# old_line_kick.net
KiCad netlist of a schematic drawn in EAGLE
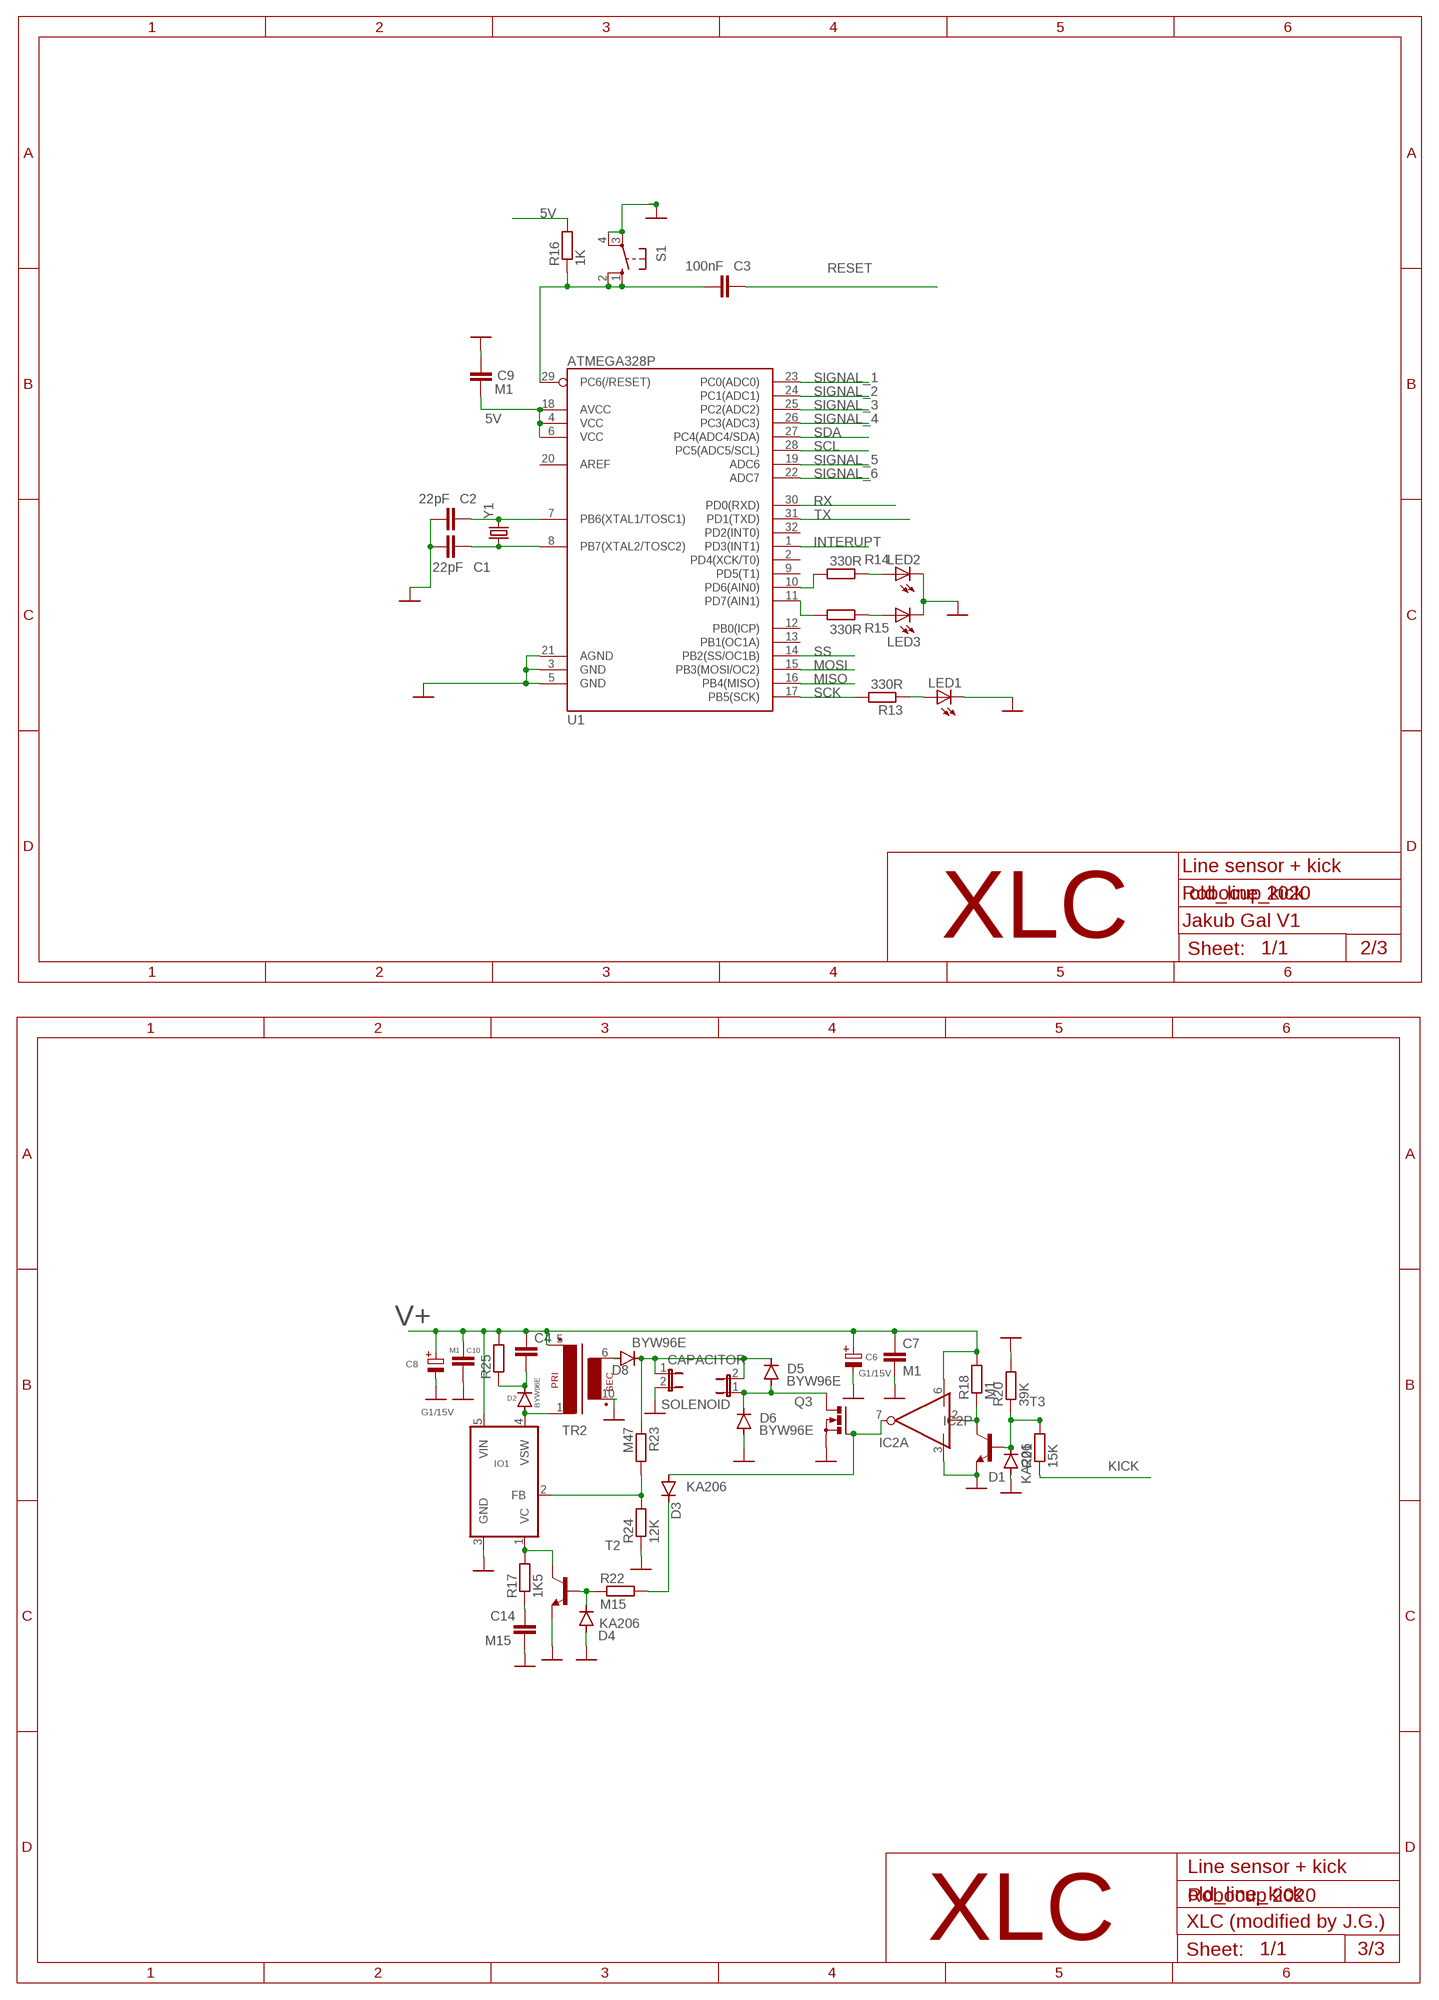
[diagram p0: schematic, sheet 1, part 1 of 2]
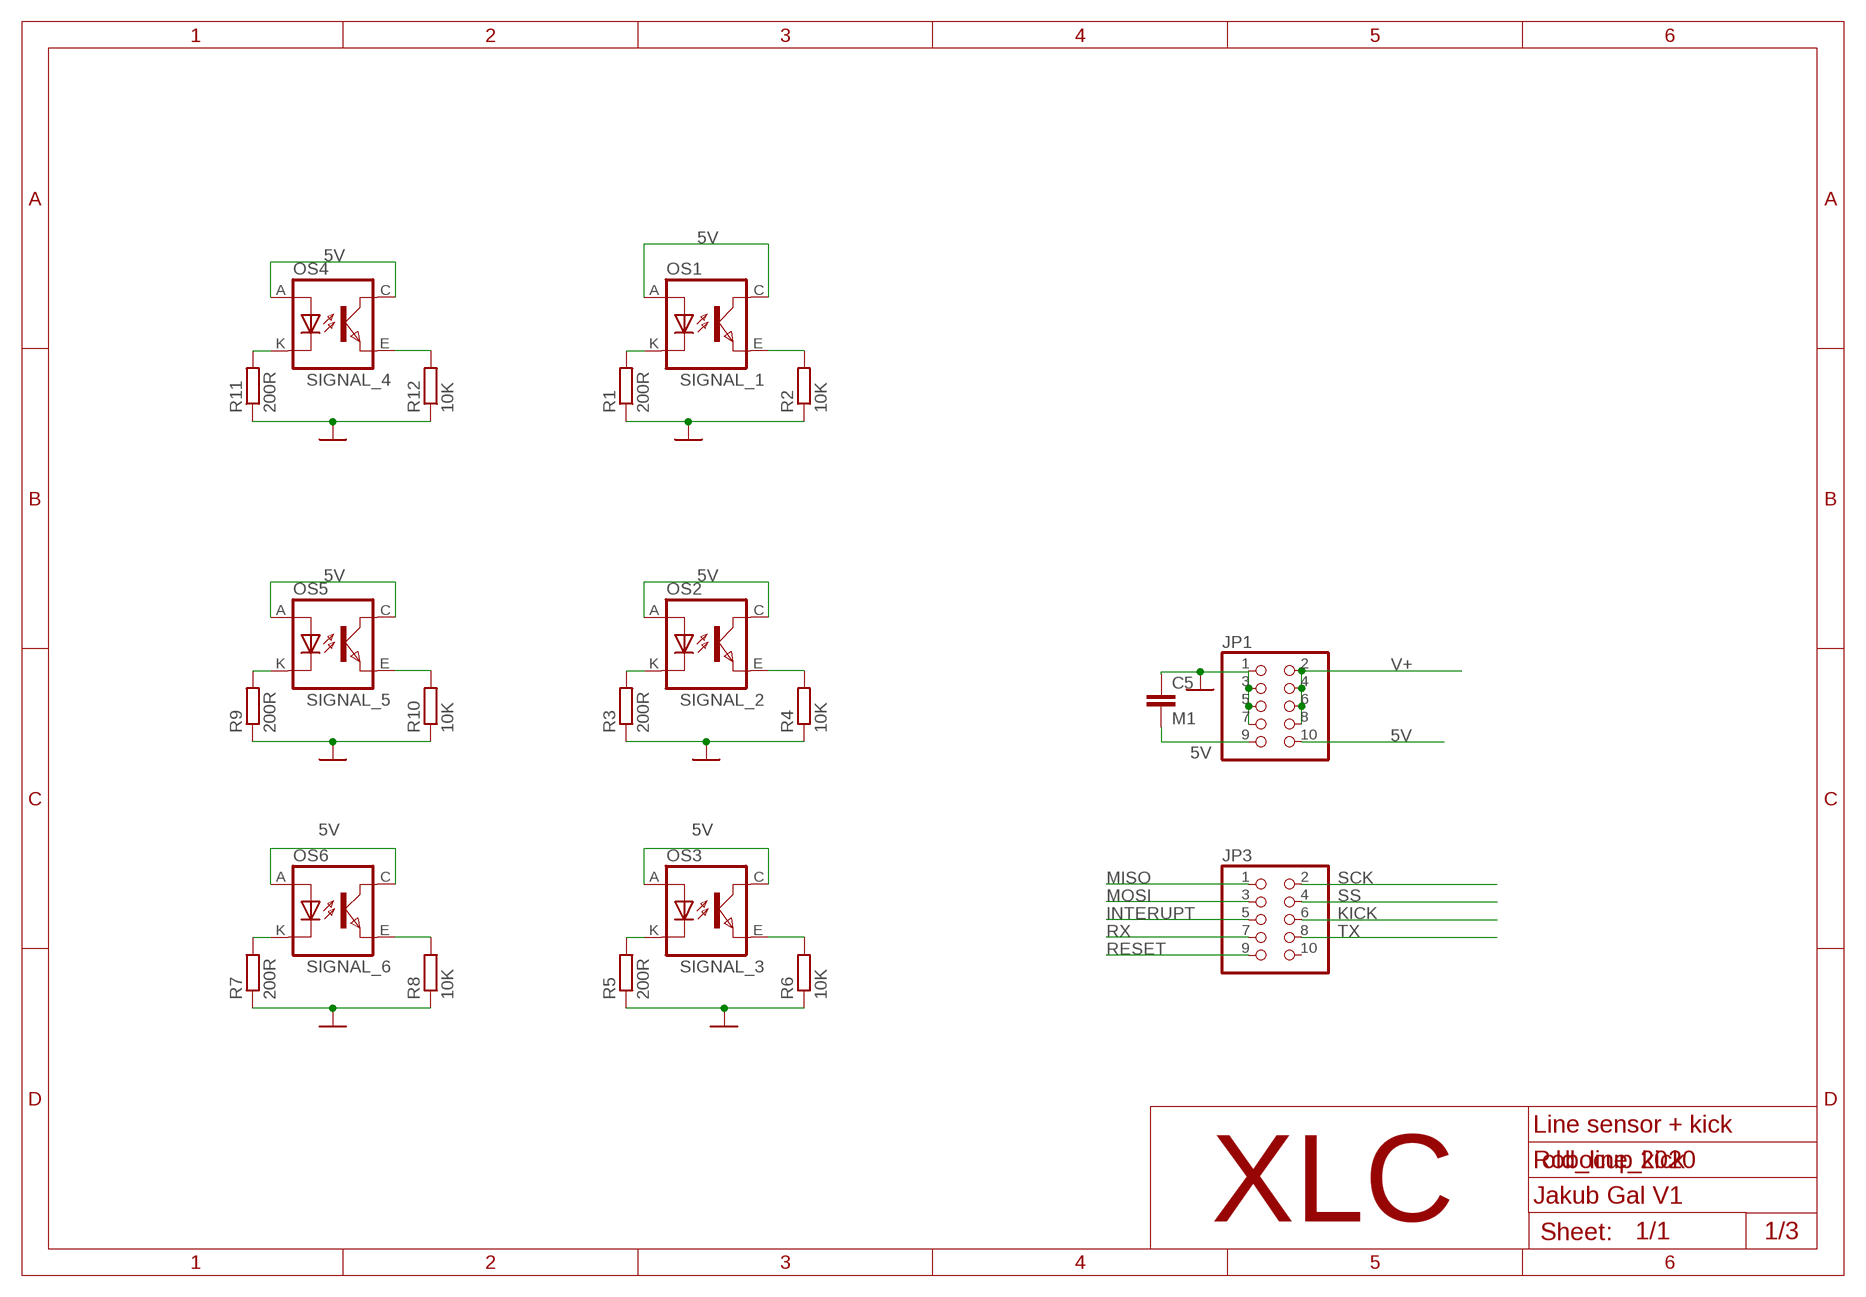
[diagram p1: schematic, sheet 1, part 2 of 2]

(export (version "E")
  (design (tool "Eeschema 10.0.6"))
  (components
    (comp (ref "C1")
      (value "22pF")
      (footprint "eagle-import:C0603")
      (libsource (lib "eagle-import") (part "rcl@1_C-EUC0603"))
    )
    (comp (ref "C2")
      (value "22pF")
      (footprint "eagle-import:C0603")
      (libsource (lib "eagle-import") (part "rcl@1_C-EUC0603"))
    )
    (comp (ref "C3")
      (value "100nF")
      (footprint "eagle-import:C0603")
      (libsource (lib "eagle-import") (part "rcl@1_C-EUC0603"))
    )
    (comp (ref "C4")
      (value "C-EU075-052X106")
      (footprint "eagle-import:C075-052X106")
      (libsource (lib "eagle-import") (part "C-EU075-052X106"))
    )
    (comp (ref "C5")
      (value "M1")
      (footprint "eagle-import:C0603")
      (libsource (lib "eagle-import") (part "C-EUC0603"))
    )
    (comp (ref "C6")
      (value "G1/15V")
      (footprint "eagle-import:E-2,5_7-RAD")
      (libsource (lib "eagle-import") (part "KOND-ELEKT-2,5/7"))
    )
    (comp (ref "C7")
      (value "M1")
      (footprint "eagle-import:C0805K")
      (libsource (lib "eagle-import") (part "resistor_C-EUC0805K"))
    )
    (comp (ref "C8")
      (value "G1/15V")
      (footprint "eagle-import:E-2,5_7-RAD")
      (libsource (lib "eagle-import") (part "KOND-ELEKT-2,5/7"))
    )
    (comp (ref "C9")
      (value "M1")
      (footprint "eagle-import:C0603")
      (libsource (lib "eagle-import") (part "rcl@1_C-EUC0603"))
    )
    (comp (ref "C10")
      (value "M1")
      (footprint "eagle-import:C0805K")
      (libsource (lib "eagle-import") (part "resistor_C-EUC0805K"))
    )
    (comp (ref "C14")
      (value "M15")
      (footprint "eagle-import:C1206")
      (libsource (lib "eagle-import") (part "resistor_C-EUC1206"))
    )
    (comp (ref "CAPACITOR")
      (value "JP1E")
      (footprint "eagle-import:JP1")
      (libsource (lib "eagle-import") (part "JP1E"))
    )
    (comp (ref "D1")
      (value "KA206")
      (footprint "eagle-import:D-7.5")
      (libsource (lib "eagle-import") (part "DIODE-D-7.5"))
    )
    (comp (ref "D2")
      (value "BYW96E")
      (footprint "eagle-import:SOD64-10")
      (libsource (lib "eagle-import") (part "BYW96"))
    )
    (comp (ref "D3")
      (value "KA206")
      (footprint "eagle-import:D-7.5")
      (libsource (lib "eagle-import") (part "DIODE-D-7.5"))
    )
    (comp (ref "D4")
      (value "KA206")
      (footprint "eagle-import:D-7.5")
      (libsource (lib "eagle-import") (part "DIODE-D-7.5"))
    )
    (comp (ref "D5")
      (value "BYW96E")
      (footprint "eagle-import:SOD64-10")
      (libsource (lib "eagle-import") (part "BYW96"))
    )
    (comp (ref "D6")
      (value "BYW96E")
      (footprint "eagle-import:SOD64-10")
      (libsource (lib "eagle-import") (part "BYW96"))
    )
    (comp (ref "D8")
      (value "BYW96E")
      (footprint "eagle-import:SOD64-10")
      (libsource (lib "eagle-import") (part "BYW96"))
    )
    (comp (ref "IC2")
      (value "MIC4423BM")
      (footprint "eagle-import:SO08")
      (libsource (lib "eagle-import") (part "MIC4423BM"))
    )
    (comp (ref "IO1")
      (value "LT1071V")
      (footprint "eagle-import:TO220-5P")
      (libsource (lib "eagle-import") (part "LT1071V"))
    )
    (comp (ref "JP1")
      (value "PINHD-2X5IDC")
      (footprint "eagle-import:2X05_IDC")
      (libsource (lib "eagle-import") (part "PINHD-2X5IDC"))
    )
    (comp (ref "JP3")
      (value "PINHD-2X5IDC")
      (footprint "eagle-import:2X05_IDC")
      (libsource (lib "eagle-import") (part "PINHD-2X5IDC"))
    )
    (comp (ref "LED1")
      (value "LEDCHIPLED_0603")
      (footprint "eagle-import:CHIPLED_0603")
      (libsource (lib "eagle-import") (part "LEDCHIPLED_0603"))
    )
    (comp (ref "LED2")
      (value "LEDCHIPLED_0603")
      (footprint "eagle-import:CHIPLED_0603")
      (libsource (lib "eagle-import") (part "LEDCHIPLED_0603"))
    )
    (comp (ref "LED3")
      (value "LEDCHIPLED_0603")
      (footprint "eagle-import:CHIPLED_0603")
      (libsource (lib "eagle-import") (part "LEDCHIPLED_0603"))
    )
    (comp (ref "OS1")
      (value "TCRT5000")
      (footprint "eagle-import:TCRT5000")
      (libsource (lib "eagle-import") (part "TCRT5000"))
    )
    (comp (ref "OS2")
      (value "TCRT5000")
      (footprint "eagle-import:TCRT5000")
      (libsource (lib "eagle-import") (part "TCRT5000"))
    )
    (comp (ref "OS3")
      (value "TCRT5000")
      (footprint "eagle-import:TCRT5000")
      (libsource (lib "eagle-import") (part "TCRT5000"))
    )
    (comp (ref "OS4")
      (value "TCRT5000")
      (footprint "eagle-import:TCRT5000")
      (fields (field (name "SPICEPREFIX") "O"))
      (libsource (lib "eagle-import") (part "TCRT5000"))
    )
    (comp (ref "OS5")
      (value "TCRT5000")
      (footprint "eagle-import:TCRT5000")
      (libsource (lib "eagle-import") (part "TCRT5000"))
    )
    (comp (ref "OS6")
      (value "TCRT5000")
      (footprint "eagle-import:TCRT5000")
      (fields (field (name "SPICEPREFIX") "O"))
      (libsource (lib "eagle-import") (part "TCRT5000"))
    )
    (comp (ref "Q3")
      (value "PMOSFET_NTO220BV")
      (footprint "eagle-import:TO220BV")
      (libsource (lib "eagle-import") (part "PMOSFET_NTO220BV"))
    )
    (comp (ref "R1")
      (value "200R")
      (footprint "eagle-import:R0603")
      (libsource (lib "eagle-import") (part "R-EU_R0603"))
    )
    (comp (ref "R2")
      (value "10K")
      (footprint "eagle-import:R0603")
      (libsource (lib "eagle-import") (part "R-EU_R0603"))
    )
    (comp (ref "R3")
      (value "200R")
      (footprint "eagle-import:R0603")
      (libsource (lib "eagle-import") (part "R-EU_R0603"))
    )
    (comp (ref "R4")
      (value "10K")
      (footprint "eagle-import:R0603")
      (libsource (lib "eagle-import") (part "R-EU_R0603"))
    )
    (comp (ref "R5")
      (value "200R")
      (footprint "eagle-import:R0603")
      (libsource (lib "eagle-import") (part "R-EU_R0603"))
    )
    (comp (ref "R6")
      (value "10K")
      (footprint "eagle-import:R0603")
      (libsource (lib "eagle-import") (part "R-EU_R0603"))
    )
    (comp (ref "R7")
      (value "200R")
      (footprint "eagle-import:R0603")
      (libsource (lib "eagle-import") (part "R-EU_R0603"))
    )
    (comp (ref "R8")
      (value "10K")
      (footprint "eagle-import:R0603")
      (libsource (lib "eagle-import") (part "R-EU_R0603"))
    )
    (comp (ref "R9")
      (value "200R")
      (footprint "eagle-import:R0603")
      (libsource (lib "eagle-import") (part "R-EU_R0603"))
    )
    (comp (ref "R10")
      (value "10K")
      (footprint "eagle-import:R0603")
      (libsource (lib "eagle-import") (part "R-EU_R0603"))
    )
    (comp (ref "R11")
      (value "200R")
      (footprint "eagle-import:R0603")
      (libsource (lib "eagle-import") (part "R-EU_R0603"))
    )
    (comp (ref "R12")
      (value "10K")
      (footprint "eagle-import:R0603")
      (libsource (lib "eagle-import") (part "R-EU_R0603"))
    )
    (comp (ref "R13")
      (value "330R")
      (footprint "eagle-import:R0603")
      (libsource (lib "eagle-import") (part "R-EU_R0603"))
    )
    (comp (ref "R14")
      (value "330R")
      (footprint "eagle-import:R0603")
      (libsource (lib "eagle-import") (part "R-EU_R0603"))
    )
    (comp (ref "R15")
      (value "330R")
      (footprint "eagle-import:R0603")
      (libsource (lib "eagle-import") (part "R-EU_R0603"))
    )
    (comp (ref "R16")
      (value "1K")
      (footprint "eagle-import:R0603")
      (libsource (lib "eagle-import") (part "R-EU_R0603"))
    )
    (comp (ref "R17")
      (value "1K5")
      (footprint "eagle-import:R1206")
      (libsource (lib "eagle-import") (part "R-EU_R1206"))
    )
    (comp (ref "R18")
      (value "M1")
      (footprint "eagle-import:R1206")
      (libsource (lib "eagle-import") (part "R-EU_R1206"))
    )
    (comp (ref "R20")
      (value "39K")
      (footprint "eagle-import:R1206")
      (libsource (lib "eagle-import") (part "R-EU_R1206"))
    )
    (comp (ref "R21")
      (value "15K")
      (footprint "eagle-import:R1206")
      (libsource (lib "eagle-import") (part "R-EU_R1206"))
    )
    (comp (ref "R22")
      (value "M15")
      (footprint "eagle-import:R1206")
      (libsource (lib "eagle-import") (part "R-EU_R1206"))
    )
    (comp (ref "R23")
      (value "M47")
      (footprint "eagle-import:R1206")
      (libsource (lib "eagle-import") (part "R-EU_R1206"))
    )
    (comp (ref "R24")
      (value "12K")
      (footprint "eagle-import:R1206")
      (libsource (lib "eagle-import") (part "R-EU_R1206"))
    )
    (comp (ref "R25")
      (value "REZISTOR-7,5MM-HORIZ")
      (footprint "eagle-import:R-7,5H")
      (libsource (lib "eagle-import") (part "REZISTOR-7,5MM-HORIZ"))
    )
    (comp (ref "S1")
      (value "10-XX")
      (footprint "eagle-import:B3F-10XX")
      (fields (field (name "MPN") "B3F-1000"))
      (libsource (lib "eagle-import") (part "10-XX"))
    )
    (comp (ref "SOLENOID")
      (value "JP1E")
      (footprint "eagle-import:JP1")
      (libsource (lib "eagle-import") (part "JP1E"))
    )
    (comp (ref "T2")
      (value "-NPN-SC59-BEC")
      (footprint "eagle-import:SC59-BEC")
      (libsource (lib "eagle-import") (part "-NPN-SC59-BEC"))
    )
    (comp (ref "T3")
      (value "-NPN-SC59-BEC")
      (footprint "eagle-import:SC59-BEC")
      (libsource (lib "eagle-import") (part "-NPN-SC59-BEC"))
    )
    (comp (ref "TR2")
      (value "TRAFO-E10-R\"\"")
      (footprint "eagle-import:TRAFO-EE17X20")
      (libsource (lib "eagle-import") (part "TRAFO-E10-R{dblquote}{dblquote}"))
    )
    (comp (ref "U1")
      (value "ATMEGA328P")
      (footprint "eagle-import:TQFP32-08")
      (libsource (lib "eagle-import") (part "ATMEGA328_SMT"))
    )
    (comp (ref "Y1")
      (value "CRYSTALHC49US")
      (footprint "eagle-import:HC49US")
      (libsource (lib "eagle-import") (part "CRYSTALHC49US"))
    )
  )
  (nets
    (net (code "1") (name "/5V") (class "Default")
      (node (ref "C5") (pin "2") (pinfunction "2_2") (pintype "passive"))
      (node (ref "C9") (pin "1") (pinfunction "1_1") (pintype "passive"))
      (node (ref "JP1") (pin "10") (pinfunction "10_10") (pintype "passive"))
      (node (ref "JP1") (pin "9") (pinfunction "9_9") (pintype "passive"))
      (node (ref "OS1") (pin "A") (pinfunction "ANODE_A") (pintype "passive"))
      (node (ref "OS1") (pin "C") (pinfunction "COLLECTOR_C") (pintype "passive"))
      (node (ref "OS2") (pin "A") (pinfunction "ANODE_A") (pintype "passive"))
      (node (ref "OS2") (pin "C") (pinfunction "COLLECTOR_C") (pintype "passive"))
      (node (ref "OS3") (pin "A") (pinfunction "ANODE_A") (pintype "passive"))
      (node (ref "OS3") (pin "C") (pinfunction "COLLECTOR_C") (pintype "passive"))
      (node (ref "OS4") (pin "A") (pinfunction "ANODE_A") (pintype "passive"))
      (node (ref "OS4") (pin "C") (pinfunction "COLLECTOR_C") (pintype "passive"))
      (node (ref "OS5") (pin "A") (pinfunction "ANODE_A") (pintype "passive"))
      (node (ref "OS5") (pin "C") (pinfunction "COLLECTOR_C") (pintype "passive"))
      (node (ref "OS6") (pin "A") (pinfunction "ANODE_A") (pintype "passive"))
      (node (ref "OS6") (pin "C") (pinfunction "COLLECTOR_C") (pintype "passive"))
      (node (ref "R16") (pin "2") (pinfunction "2_2") (pintype "passive"))
      (node (ref "U1") (pin "18") (pinfunction "AVCC_18") (pintype "bidirectional"))
      (node (ref "U1") (pin "4") (pinfunction "VCC_4") (pintype "bidirectional"))
      (node (ref "U1") (pin "6") (pinfunction "VCC_6") (pintype "bidirectional"))
    )
    (net (code "2") (name "/INTERUPT") (class "Default")
      (node (ref "JP3") (pin "5") (pinfunction "5_5") (pintype "passive"))
      (node (ref "U1") (pin "1") (pinfunction "PD3(INT1)_1") (pintype "bidirectional"))
    )
    (net (code "3") (name "/KICK") (class "Default")
      (node (ref "JP3") (pin "6") (pinfunction "6_6") (pintype "passive"))
      (node (ref "R21") (pin "1") (pinfunction "1_1") (pintype "passive"))
    )
    (net (code "4") (name "/MISO") (class "Default")
      (node (ref "JP3") (pin "1") (pinfunction "1_1") (pintype "passive"))
      (node (ref "U1") (pin "16") (pinfunction "PB4(MISO)_16") (pintype "bidirectional"))
    )
    (net (code "5") (name "/MOSI") (class "Default")
      (node (ref "JP3") (pin "3") (pinfunction "3_3") (pintype "passive"))
      (node (ref "U1") (pin "15") (pinfunction "PB3(MOSI/OC2)_15") (pintype "bidirectional"))
    )
    (net (code "6") (name "/RESET") (class "Default")
      (node (ref "C3") (pin "2") (pinfunction "2_2") (pintype "passive"))
      (node (ref "JP3") (pin "9") (pinfunction "9_9") (pintype "passive"))
    )
    (net (code "7") (name "/RX") (class "Default")
      (node (ref "JP3") (pin "7") (pinfunction "7_7") (pintype "passive"))
      (node (ref "U1") (pin "30") (pinfunction "PD0(RXD)_30") (pintype "bidirectional"))
    )
    (net (code "8") (name "/SCK") (class "Default")
      (node (ref "JP3") (pin "2") (pinfunction "2_2") (pintype "passive"))
      (node (ref "R13") (pin "2") (pinfunction "2_2") (pintype "passive"))
      (node (ref "U1") (pin "17") (pinfunction "PB5(SCK)_17") (pintype "bidirectional"))
    )
    (net (code "9") (name "/SCL") (class "Default")
      (node (ref "U1") (pin "28") (pinfunction "PC5(ADC5/SCL)_28") (pintype "bidirectional"))
    )
    (net (code "10") (name "/SDA") (class "Default")
      (node (ref "U1") (pin "27") (pinfunction "PC4(ADC4/SDA)_27") (pintype "bidirectional"))
    )
    (net (code "11") (name "/SIGNAL_1") (class "Default")
      (node (ref "OS1") (pin "E") (pinfunction "EMITTER_E") (pintype "passive"))
      (node (ref "R2") (pin "2") (pinfunction "2_2") (pintype "passive"))
      (node (ref "U1") (pin "23") (pinfunction "PC0(ADC0)_23") (pintype "bidirectional"))
    )
    (net (code "12") (name "/SIGNAL_2") (class "Default")
      (node (ref "OS2") (pin "E") (pinfunction "EMITTER_E") (pintype "passive"))
      (node (ref "R4") (pin "2") (pinfunction "2_2") (pintype "passive"))
      (node (ref "U1") (pin "24") (pinfunction "PC1(ADC1)_24") (pintype "bidirectional"))
    )
    (net (code "13") (name "/SIGNAL_3") (class "Default")
      (node (ref "OS3") (pin "E") (pinfunction "EMITTER_E") (pintype "passive"))
      (node (ref "R6") (pin "2") (pinfunction "2_2") (pintype "passive"))
      (node (ref "U1") (pin "25") (pinfunction "PC2(ADC2)_25") (pintype "bidirectional"))
    )
    (net (code "14") (name "/SIGNAL_4") (class "Default")
      (node (ref "OS4") (pin "E") (pinfunction "EMITTER_E") (pintype "passive"))
      (node (ref "R12") (pin "2") (pinfunction "2_2") (pintype "passive"))
      (node (ref "U1") (pin "26") (pinfunction "PC3(ADC3)_26") (pintype "bidirectional"))
    )
    (net (code "15") (name "/SIGNAL_5") (class "Default")
      (node (ref "OS5") (pin "E") (pinfunction "EMITTER_E") (pintype "passive"))
      (node (ref "R10") (pin "2") (pinfunction "2_2") (pintype "passive"))
      (node (ref "U1") (pin "19") (pinfunction "ADC6_19") (pintype "bidirectional"))
    )
    (net (code "16") (name "/SIGNAL_6") (class "Default")
      (node (ref "OS6") (pin "E") (pinfunction "EMITTER_E") (pintype "passive"))
      (node (ref "R8") (pin "2") (pinfunction "2_2") (pintype "passive"))
      (node (ref "U1") (pin "22") (pinfunction "ADC7_22") (pintype "bidirectional"))
    )
    (net (code "17") (name "/SS") (class "Default")
      (node (ref "JP3") (pin "4") (pinfunction "4_4") (pintype "passive"))
      (node (ref "U1") (pin "14") (pinfunction "PB2(SS/OC1B)_14") (pintype "bidirectional"))
    )
    (net (code "18") (name "/TX") (class "Default")
      (node (ref "JP3") (pin "8") (pinfunction "8_8") (pintype "passive"))
      (node (ref "U1") (pin "31") (pinfunction "PD1(TXD)_31") (pintype "bidirectional"))
    )
    (net (code "19") (name "/V+") (class "Default")
      (node (ref "C10") (pin "1") (pinfunction "1_1") (pintype "passive"))
      (node (ref "C4") (pin "1") (pinfunction "1_1") (pintype "passive"))
      (node (ref "C6") (pin "+") (pinfunction "+_+") (pintype "passive"))
      (node (ref "C7") (pin "1") (pinfunction "1_1") (pintype "passive"))
      (node (ref "C8") (pin "+") (pinfunction "+_+") (pintype "passive"))
      (node (ref "IC2") (pin "6") (pinfunction "V+_6") (pintype "power_in"))
      (node (ref "IO1") (pin "5") (pinfunction "VIN_5") (pintype "power_in"))
      (node (ref "JP1") (pin "2") (pinfunction "2_2") (pintype "passive"))
      (node (ref "JP1") (pin "4") (pinfunction "4_4") (pintype "passive"))
      (node (ref "JP1") (pin "6") (pinfunction "6_6") (pintype "passive"))
      (node (ref "JP1") (pin "8") (pinfunction "8_8") (pintype "passive"))
      (node (ref "R18") (pin "2") (pinfunction "2_2") (pintype "passive"))
      (node (ref "R25") (pin "2") (pinfunction "2_2") (pintype "passive"))
      (node (ref "TR2") (pin "5") (pinfunction "2_5") (pintype "passive"))
    )
    (net (code "20") (name "GND") (class "Default")
      (node (ref "C1") (pin "1") (pinfunction "1_1") (pintype "passive"))
      (node (ref "C10") (pin "2") (pinfunction "2_2") (pintype "passive"))
      (node (ref "C14") (pin "2") (pinfunction "2_2") (pintype "passive"))
      (node (ref "C2") (pin "1") (pinfunction "1_1") (pintype "passive"))
      (node (ref "C5") (pin "1") (pinfunction "1_1") (pintype "passive"))
      (node (ref "C6") (pin "-") (pinfunction "-_-") (pintype "passive"))
      (node (ref "C7") (pin "2") (pinfunction "2_2") (pintype "passive"))
      (node (ref "C8") (pin "-") (pinfunction "-_-") (pintype "passive"))
      (node (ref "C9") (pin "2") (pinfunction "2_2") (pintype "passive"))
      (node (ref "CAPACITOR") (pin "2") (pinfunction "2_2") (pintype "passive"))
      (node (ref "D1") (pin "A") (pinfunction "A_A") (pintype "passive"))
      (node (ref "D4") (pin "A") (pinfunction "A_A") (pintype "passive"))
      (node (ref "D6") (pin "A") (pinfunction "A_A") (pintype "passive"))
      (node (ref "IC2") (pin "3") (pinfunction "GND_3") (pintype "power_in"))
      (node (ref "IO1") (pin "3") (pinfunction "GND_3") (pintype "power_in"))
      (node (ref "JP1") (pin "1") (pinfunction "1_1") (pintype "passive"))
      (node (ref "JP1") (pin "3") (pinfunction "3_3") (pintype "passive"))
      (node (ref "JP1") (pin "5") (pinfunction "5_5") (pintype "passive"))
      (node (ref "JP1") (pin "7") (pinfunction "7_7") (pintype "passive"))
      (node (ref "LED1") (pin "C") (pinfunction "C_C") (pintype "passive"))
      (node (ref "LED2") (pin "C") (pinfunction "C_C") (pintype "passive"))
      (node (ref "LED3") (pin "C") (pinfunction "C_C") (pintype "passive"))
      (node (ref "Q3") (pin "S") (pinfunction "S_S") (pintype "passive"))
      (node (ref "R1") (pin "1") (pinfunction "1_1") (pintype "passive"))
      (node (ref "R10") (pin "1") (pinfunction "1_1") (pintype "passive"))
      (node (ref "R11") (pin "1") (pinfunction "1_1") (pintype "passive"))
      (node (ref "R12") (pin "1") (pinfunction "1_1") (pintype "passive"))
      (node (ref "R2") (pin "1") (pinfunction "1_1") (pintype "passive"))
      (node (ref "R20") (pin "2") (pinfunction "2_2") (pintype "passive"))
      (node (ref "R24") (pin "1") (pinfunction "1_1") (pintype "passive"))
      (node (ref "R3") (pin "1") (pinfunction "1_1") (pintype "passive"))
      (node (ref "R4") (pin "1") (pinfunction "1_1") (pintype "passive"))
      (node (ref "R5") (pin "1") (pinfunction "1_1") (pintype "passive"))
      (node (ref "R6") (pin "1") (pinfunction "1_1") (pintype "passive"))
      (node (ref "R7") (pin "1") (pinfunction "1_1") (pintype "passive"))
      (node (ref "R8") (pin "1") (pinfunction "1_1") (pintype "passive"))
      (node (ref "R9") (pin "1") (pinfunction "1_1") (pintype "passive"))
      (node (ref "S1") (pin "3") (pinfunction "P_3") (pintype "passive"))
      (node (ref "S1") (pin "4") (pinfunction "P1_4") (pintype "passive"))
      (node (ref "T2") (pin "E") (pinfunction "E_E") (pintype "passive"))
      (node (ref "T3") (pin "E") (pinfunction "E_E") (pintype "passive"))
      (node (ref "TR2") (pin "10") (pinfunction "4_10") (pintype "passive"))
      (node (ref "U1") (pin "21") (pinfunction "AGND_21") (pintype "bidirectional"))
      (node (ref "U1") (pin "3") (pinfunction "GND_3") (pintype "bidirectional"))
      (node (ref "U1") (pin "5") (pinfunction "GND_5") (pintype "bidirectional"))
    )
    (net (code "21") (name "Net-(C4-Pad2)") (class "Default")
      (node (ref "C4") (pin "2") (pinfunction "2_2") (pintype "passive"))
      (node (ref "D2") (pin "C") (pinfunction "C_C") (pintype "passive"))
      (node (ref "R25") (pin "1") (pinfunction "1_1") (pintype "passive"))
    )
    (net (code "22") (name "Net-(C14-Pad1)") (class "Default")
      (node (ref "C14") (pin "1") (pinfunction "1_1") (pintype "passive"))
      (node (ref "R17") (pin "1") (pinfunction "1_1") (pintype "passive"))
    )
    (net (code "23") (name "Net-(CAPACITOR-Pad1)") (class "Default")
      (node (ref "CAPACITOR") (pin "1") (pinfunction "1_1") (pintype "passive"))
      (node (ref "D5") (pin "C") (pinfunction "C_C") (pintype "passive"))
      (node (ref "D8") (pin "C") (pinfunction "C_C") (pintype "passive"))
      (node (ref "R23") (pin "1") (pinfunction "1_1") (pintype "passive"))
      (node (ref "SOLENOID") (pin "2") (pinfunction "2_2") (pintype "passive"))
    )
    (net (code "24") (name "Net-(D1-PadC)") (class "Default")
      (node (ref "D1") (pin "C") (pinfunction "C_C") (pintype "passive"))
      (node (ref "R20") (pin "1") (pinfunction "1_1") (pintype "passive"))
      (node (ref "R21") (pin "2") (pinfunction "2_2") (pintype "passive"))
      (node (ref "T3") (pin "B") (pinfunction "B_B") (pintype "passive"))
    )
    (net (code "25") (name "Net-(D3-PadC)") (class "Default")
      (node (ref "D3") (pin "C") (pinfunction "C_C") (pintype "passive"))
      (node (ref "R22") (pin "2") (pinfunction "2_2") (pintype "passive"))
    )
    (net (code "26") (name "Net-(D4-PadC)") (class "Default")
      (node (ref "D4") (pin "C") (pinfunction "C_C") (pintype "passive"))
      (node (ref "R22") (pin "1") (pinfunction "1_1") (pintype "passive"))
      (node (ref "T2") (pin "B") (pinfunction "B_B") (pintype "passive"))
    )
    (net (code "27") (name "Net-(D5-PadA)") (class "Default")
      (node (ref "D5") (pin "A") (pinfunction "A_A") (pintype "passive"))
      (node (ref "D6") (pin "C") (pinfunction "C_C") (pintype "passive"))
      (node (ref "Q3") (pin "D") (pinfunction "D_D") (pintype "passive"))
      (node (ref "SOLENOID") (pin "1") (pinfunction "1_1") (pintype "passive"))
    )
    (net (code "28") (name "Net-(IC2A-IN)") (class "Default")
      (node (ref "IC2") (pin "2") (pinfunction "IN_2") (pintype "input"))
      (node (ref "R18") (pin "1") (pinfunction "1_1") (pintype "passive"))
      (node (ref "T3") (pin "C") (pinfunction "C_C") (pintype "passive"))
    )
    (net (code "29") (name "Net-(IC2A-OUT)") (class "Default")
      (node (ref "D3") (pin "A") (pinfunction "A_A") (pintype "passive"))
      (node (ref "IC2") (pin "7") (pinfunction "OUT_7") (pintype "output"))
      (node (ref "Q3") (pin "G") (pinfunction "G_G") (pintype "passive"))
    )
    (net (code "30") (name "Net-(IO1-FB)") (class "Default")
      (node (ref "IO1") (pin "2") (pinfunction "FB_2") (pintype "input"))
      (node (ref "R23") (pin "2") (pinfunction "2_2") (pintype "passive"))
      (node (ref "R24") (pin "2") (pinfunction "2_2") (pintype "passive"))
    )
    (net (code "31") (name "Net-(IO1-VC)") (class "Default")
      (node (ref "IO1") (pin "1") (pinfunction "VC_1") (pintype "input"))
      (node (ref "R17") (pin "2") (pinfunction "2_2") (pintype "passive"))
      (node (ref "T2") (pin "C") (pinfunction "C_C") (pintype "passive"))
    )
    (net (code "32") (name "Net-(IO1-VSW)") (class "Default")
      (node (ref "D2") (pin "A") (pinfunction "A_A") (pintype "passive"))
      (node (ref "IO1") (pin "4") (pinfunction "VSW_4") (pintype "output"))
      (node (ref "TR2") (pin "1") (pinfunction "1_1") (pintype "passive"))
    )
    (net (code "33") (name "Net-(LED1-PadA)") (class "Default")
      (node (ref "LED1") (pin "A") (pinfunction "A_A") (pintype "passive"))
      (node (ref "R13") (pin "1") (pinfunction "1_1") (pintype "passive"))
    )
    (net (code "34") (name "Net-(LED2-PadA)") (class "Default")
      (node (ref "LED2") (pin "A") (pinfunction "A_A") (pintype "passive"))
      (node (ref "R14") (pin "1") (pinfunction "1_1") (pintype "passive"))
    )
    (net (code "35") (name "Net-(LED3-PadA)") (class "Default")
      (node (ref "LED3") (pin "A") (pinfunction "A_A") (pintype "passive"))
      (node (ref "R15") (pin "1") (pinfunction "1_1") (pintype "passive"))
    )
    (net (code "36") (name "Net-(OS1-CATHODE)") (class "Default")
      (node (ref "OS1") (pin "K") (pinfunction "CATHODE_K") (pintype "passive"))
      (node (ref "R1") (pin "2") (pinfunction "2_2") (pintype "passive"))
    )
    (net (code "37") (name "Net-(OS2-CATHODE)") (class "Default")
      (node (ref "OS2") (pin "K") (pinfunction "CATHODE_K") (pintype "passive"))
      (node (ref "R3") (pin "2") (pinfunction "2_2") (pintype "passive"))
    )
    (net (code "38") (name "Net-(OS3-CATHODE)") (class "Default")
      (node (ref "OS3") (pin "K") (pinfunction "CATHODE_K") (pintype "passive"))
      (node (ref "R5") (pin "2") (pinfunction "2_2") (pintype "passive"))
    )
    (net (code "39") (name "Net-(OS4-CATHODE)") (class "Default")
      (node (ref "OS4") (pin "K") (pinfunction "CATHODE_K") (pintype "passive"))
      (node (ref "R11") (pin "2") (pinfunction "2_2") (pintype "passive"))
    )
    (net (code "40") (name "Net-(OS5-CATHODE)") (class "Default")
      (node (ref "OS5") (pin "K") (pinfunction "CATHODE_K") (pintype "passive"))
      (node (ref "R9") (pin "2") (pinfunction "2_2") (pintype "passive"))
    )
    (net (code "41") (name "Net-(OS6-CATHODE)") (class "Default")
      (node (ref "OS6") (pin "K") (pinfunction "CATHODE_K") (pintype "passive"))
      (node (ref "R7") (pin "2") (pinfunction "2_2") (pintype "passive"))
    )
    (net (code "42") (name "Net-(S1-S)") (class "Default")
      (node (ref "C3") (pin "1") (pinfunction "1_1") (pintype "passive"))
      (node (ref "R16") (pin "1") (pinfunction "1_1") (pintype "passive"))
      (node (ref "S1") (pin "1") (pinfunction "S_1") (pintype "passive"))
      (node (ref "S1") (pin "2") (pinfunction "S1_2") (pintype "passive"))
      (node (ref "U1") (pin "29") (pinfunction "PC6(/RESET)_29") (pintype "bidirectional"))
    )
    (net (code "43") (name "Net-(TR2-3)") (class "Default")
      (node (ref "D8") (pin "A") (pinfunction "A_A") (pintype "passive"))
      (node (ref "TR2") (pin "6") (pinfunction "3_6") (pintype "passive"))
    )
    (net (code "44") (name "Net-(U1-PB6(XTAL1{slash}TOSC1))") (class "Default")
      (node (ref "C2") (pin "2") (pinfunction "2_2") (pintype "passive"))
      (node (ref "U1") (pin "7") (pinfunction "PB6(XTAL1/TOSC1)_7") (pintype "bidirectional"))
      (node (ref "Y1") (pin "2") (pinfunction "2_2") (pintype "passive"))
    )
    (net (code "45") (name "Net-(U1-PB7(XTAL2{slash}TOSC2))") (class "Default")
      (node (ref "C1") (pin "2") (pinfunction "2_2") (pintype "passive"))
      (node (ref "U1") (pin "8") (pinfunction "PB7(XTAL2/TOSC2)_8") (pintype "bidirectional"))
      (node (ref "Y1") (pin "1") (pinfunction "1_1") (pintype "passive"))
    )
    (net (code "46") (name "Net-(U1-PD6(AIN0))") (class "Default")
      (node (ref "R14") (pin "2") (pinfunction "2_2") (pintype "passive"))
      (node (ref "U1") (pin "10") (pinfunction "PD6(AIN0)_10") (pintype "bidirectional"))
    )
    (net (code "47") (name "Net-(U1-PD7(AIN1))") (class "Default")
      (node (ref "R15") (pin "2") (pinfunction "2_2") (pintype "passive"))
      (node (ref "U1") (pin "11") (pinfunction "PD7(AIN1)_11") (pintype "bidirectional"))
    )
    (net (code "48") (name "unconnected-(JP3-Pad10)") (class "Default")
      (node (ref "JP3") (pin "10") (pinfunction "10_10") (pintype "passive"))
    )
    (net (code "49") (name "unconnected-(U1-AREF-Pad20)") (class "Default")
      (node (ref "U1") (pin "20") (pinfunction "AREF_20") (pintype "bidirectional"))
    )
    (net (code "50") (name "unconnected-(U1-PB0(ICP)-Pad12)") (class "Default")
      (node (ref "U1") (pin "12") (pinfunction "PB0(ICP)_12") (pintype "bidirectional"))
    )
    (net (code "51") (name "unconnected-(U1-PB1(OC1A)-Pad13)") (class "Default")
      (node (ref "U1") (pin "13") (pinfunction "PB1(OC1A)_13") (pintype "bidirectional"))
    )
    (net (code "52") (name "unconnected-(U1-PD2(INT0)-Pad32)") (class "Default")
      (node (ref "U1") (pin "32") (pinfunction "PD2(INT0)_32") (pintype "bidirectional"))
    )
    (net (code "53") (name "unconnected-(U1-PD4(XCK{slash}T0)-Pad2)") (class "Default")
      (node (ref "U1") (pin "2") (pinfunction "PD4(XCK/T0)_2") (pintype "bidirectional"))
    )
    (net (code "54") (name "unconnected-(U1-PD5(T1)-Pad9)") (class "Default")
      (node (ref "U1") (pin "9") (pinfunction "PD5(T1)_9") (pintype "bidirectional"))
    )
  )
)
